# ByrneLite.net
KiCad netlist of a schematic drawn in EAGLE
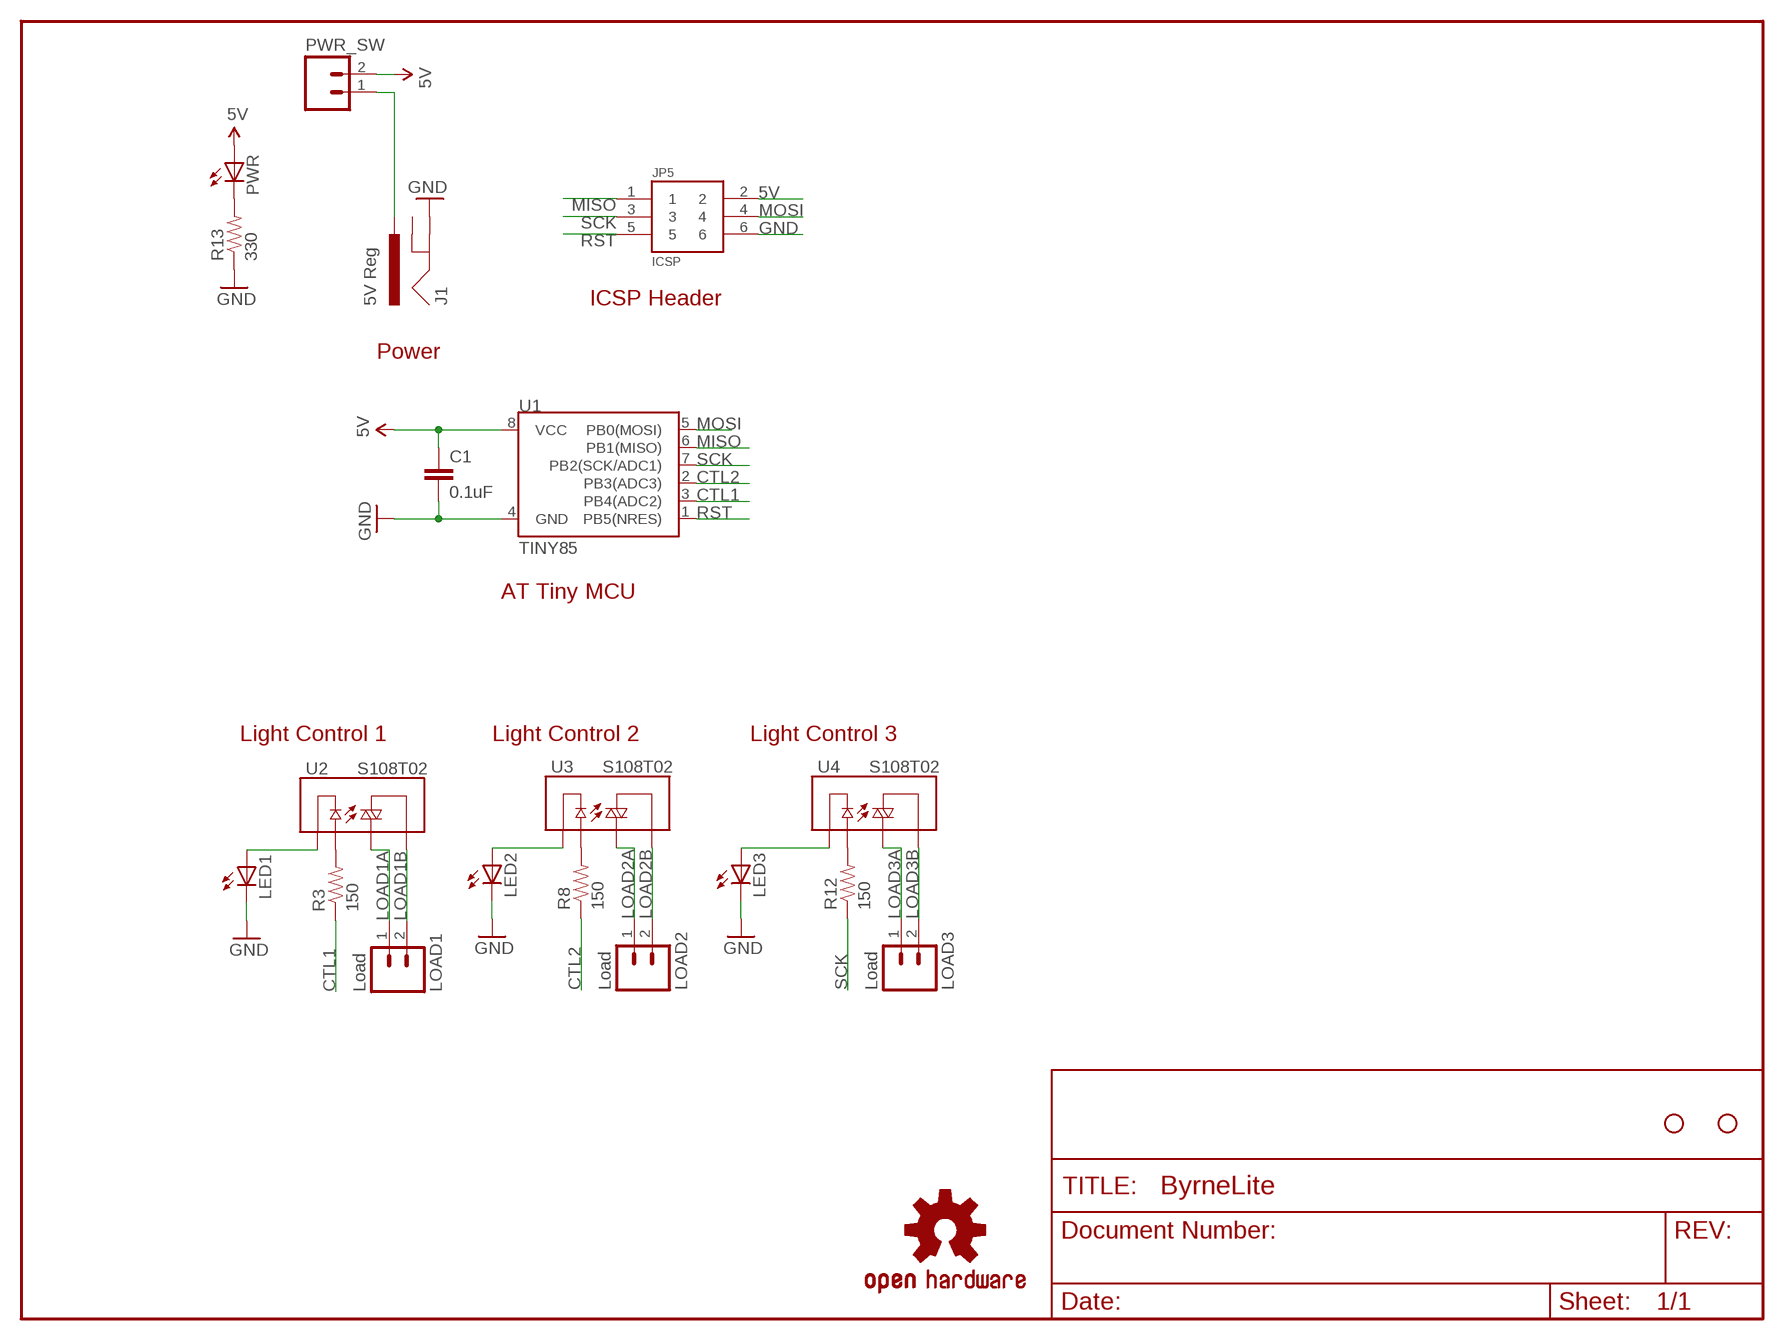
[diagram p0: schematic, sheet 1]

(export (version "E")
  (design (tool "Eeschema 10.0.6"))
  (components
    (comp (ref "C1")
      (value "0.1uF")
      (footprint "eagle-import:CAP-PTH-SMALL2")
      (libsource (lib "eagle-import") (part "CAPPTH2"))
    )
    (comp (ref "J1")
      (value "5V Reg")
      (footprint "eagle-import:POWER_JACK_PTH_LOCK")
      (libsource (lib "eagle-import") (part "POWER_JACKPTH_LOCK"))
    )
    (comp (ref "JP5")
      (value "ICSP")
      (footprint "eagle-import:2X3-SHROUDED")
      (libsource (lib "eagle-import") (part "M03X2"))
    )
    (comp (ref "LED1")
      (value "LED5MM")
      (footprint "eagle-import:LED5MM")
      (libsource (lib "eagle-import") (part "LED5MM"))
    )
    (comp (ref "LED2")
      (value "LED5MM")
      (footprint "eagle-import:LED5MM")
      (libsource (lib "eagle-import") (part "LED5MM"))
    )
    (comp (ref "LED3")
      (value "LED5MM")
      (footprint "eagle-import:LED5MM")
      (libsource (lib "eagle-import") (part "LED5MM"))
    )
    (comp (ref "LOAD1")
      (value "Load")
      (footprint "eagle-import:SCREWTERMINAL-5MM-2")
      (libsource (lib "eagle-import") (part "M025MM"))
    )
    (comp (ref "LOAD2")
      (value "Load")
      (footprint "eagle-import:SCREWTERMINAL-5MM-2")
      (libsource (lib "eagle-import") (part "M025MM"))
    )
    (comp (ref "LOAD3")
      (value "Load")
      (footprint "eagle-import:SCREWTERMINAL-5MM-2")
      (libsource (lib "eagle-import") (part "M025MM"))
    )
    (comp (ref "LOGO1")
      (value "OSHW-LOGOM")
      (footprint "eagle-import:OSHW-LOGO-M")
      (libsource (lib "eagle-import") (part "OSHW-LOGOM"))
    )
    (comp (ref "PWR")
      (value "LED3MM")
      (footprint "eagle-import:LED3MM")
      (libsource (lib "eagle-import") (part "LED3MM"))
    )
    (comp (ref "PWR_SW")
      (value "M02PTH3")
      (footprint "eagle-import:1X02_LONGPADS")
      (libsource (lib "eagle-import") (part "SparkFun-Connectors_M02PTH3"))
    )
    (comp (ref "R3")
      (value "150")
      (footprint "eagle-import:AXIAL-0.3")
      (libsource (lib "eagle-import") (part "RESISTORAXIAL-0.3"))
    )
    (comp (ref "R8")
      (value "150")
      (footprint "eagle-import:AXIAL-0.3")
      (libsource (lib "eagle-import") (part "RESISTORAXIAL-0.3"))
    )
    (comp (ref "R12")
      (value "150")
      (footprint "eagle-import:AXIAL-0.3")
      (libsource (lib "eagle-import") (part "RESISTORAXIAL-0.3"))
    )
    (comp (ref "R13")
      (value "330")
      (footprint "eagle-import:AXIAL-0.3")
      (libsource (lib "eagle-import") (part "RESISTORAXIAL-0.3"))
    )
    (comp (ref "STANDOFF2")
      (value "STAND-OFF")
      (footprint "eagle-import:STAND-OFF")
      (libsource (lib "eagle-import") (part "STAND-OFF"))
    )
    (comp (ref "STANDOFF4")
      (value "STAND-OFF")
      (footprint "eagle-import:STAND-OFF")
      (libsource (lib "eagle-import") (part "STAND-OFF"))
    )
    (comp (ref "U1")
      (value "TINY85")
      (footprint "eagle-import:DIP08")
      (fields (field (name "PROD_ID") "IC-09445"))
      (libsource (lib "eagle-import") (part "ATTINY45TINY85-20-DIP"))
    )
    (comp (ref "U2")
      (value "S108T02")
      (footprint "eagle-import:RELAY-S108T02")
      (libsource (lib "eagle-import") (part "RELAY-SOLIDSTATEPTH"))
    )
    (comp (ref "U3")
      (value "S108T02")
      (footprint "eagle-import:RELAY-S108T02")
      (libsource (lib "eagle-import") (part "RELAY-SOLIDSTATEPTH"))
    )
    (comp (ref "U4")
      (value "S108T02")
      (footprint "eagle-import:RELAY-S108T02")
      (libsource (lib "eagle-import") (part "RELAY-SOLIDSTATEPTH"))
    )
  )
  (nets
    (net (code "1") (name "/CTL1") (class "Default")
      (node (ref "R3") (pin "P$1") (pinfunction "1_P$1") (pintype "passive"))
      (node (ref "U1") (pin "3") (pinfunction "PB4(ADC2)_3") (pintype "bidirectional"))
    )
    (net (code "2") (name "/CTL2") (class "Default")
      (node (ref "R8") (pin "P$1") (pinfunction "1_P$1") (pintype "passive"))
      (node (ref "U1") (pin "2") (pinfunction "PB3(ADC3)_2") (pintype "bidirectional"))
    )
    (net (code "3") (name "/LOAD1A") (class "Default")
      (node (ref "LOAD1") (pin "1") (pinfunction "1_1") (pintype "passive"))
      (node (ref "U2") (pin "2") (pinfunction "T2_2") (pintype "bidirectional"))
    )
    (net (code "4") (name "/LOAD1B") (class "Default")
      (node (ref "LOAD1") (pin "2") (pinfunction "2_2") (pintype "passive"))
      (node (ref "U2") (pin "1") (pinfunction "T1_1") (pintype "bidirectional"))
    )
    (net (code "5") (name "/LOAD2A") (class "Default")
      (node (ref "LOAD2") (pin "1") (pinfunction "1_1") (pintype "passive"))
      (node (ref "U3") (pin "2") (pinfunction "T2_2") (pintype "bidirectional"))
    )
    (net (code "6") (name "/LOAD2B") (class "Default")
      (node (ref "LOAD2") (pin "2") (pinfunction "2_2") (pintype "passive"))
      (node (ref "U3") (pin "1") (pinfunction "T1_1") (pintype "bidirectional"))
    )
    (net (code "7") (name "/LOAD3A") (class "Default")
      (node (ref "LOAD3") (pin "1") (pinfunction "1_1") (pintype "passive"))
      (node (ref "U4") (pin "2") (pinfunction "T2_2") (pintype "bidirectional"))
    )
    (net (code "8") (name "/LOAD3B") (class "Default")
      (node (ref "LOAD3") (pin "2") (pinfunction "2_2") (pintype "passive"))
      (node (ref "U4") (pin "1") (pinfunction "T1_1") (pintype "bidirectional"))
    )
    (net (code "9") (name "/MISO") (class "Default")
      (node (ref "JP5") (pin "1") (pinfunction "1_1") (pintype "bidirectional"))
      (node (ref "U1") (pin "6") (pinfunction "PB1(MISO)_6") (pintype "bidirectional"))
    )
    (net (code "10") (name "/MOSI") (class "Default")
      (node (ref "JP5") (pin "4") (pinfunction "4_4") (pintype "bidirectional"))
      (node (ref "U1") (pin "5") (pinfunction "PB0(MOSI)_5") (pintype "bidirectional"))
    )
    (net (code "11") (name "/RST") (class "Default")
      (node (ref "JP5") (pin "5") (pinfunction "5_5") (pintype "bidirectional"))
      (node (ref "U1") (pin "1") (pinfunction "PB5(NRES)_1") (pintype "bidirectional"))
    )
    (net (code "12") (name "/SCK") (class "Default")
      (node (ref "JP5") (pin "3") (pinfunction "3_3") (pintype "bidirectional"))
      (node (ref "R12") (pin "P$1") (pinfunction "1_P$1") (pintype "passive"))
      (node (ref "U1") (pin "7") (pinfunction "PB2(SCK/ADC1)_7") (pintype "bidirectional"))
    )
    (net (code "13") (name "5V") (class "Default")
      (node (ref "C1") (pin "1") (pinfunction "1_1") (pintype "passive"))
      (node (ref "JP5") (pin "2") (pinfunction "2_2") (pintype "bidirectional"))
      (node (ref "PWR") (pin "A") (pinfunction "A_A") (pintype "passive"))
      (node (ref "PWR_SW") (pin "2") (pinfunction "2_2") (pintype "passive"))
      (node (ref "U1") (pin "8") (pinfunction "VCC_8") (pintype "bidirectional"))
    )
    (net (code "14") (name "GND") (class "Default")
      (node (ref "C1") (pin "2") (pinfunction "2_2") (pintype "passive"))
      (node (ref "J1") (pin "GND") (pinfunction "GND_GND") (pintype "bidirectional"))
      (node (ref "JP5") (pin "6") (pinfunction "6_6") (pintype "bidirectional"))
      (node (ref "LED1") (pin "K") (pinfunction "C_K") (pintype "passive"))
      (node (ref "LED2") (pin "K") (pinfunction "C_K") (pintype "passive"))
      (node (ref "LED3") (pin "K") (pinfunction "C_K") (pintype "passive"))
      (node (ref "R13") (pin "P$1") (pinfunction "1_P$1") (pintype "passive"))
      (node (ref "U1") (pin "4") (pinfunction "GND_4") (pintype "bidirectional"))
    )
    (net (code "15") (name "Net-(J1-PadPWR)") (class "Default")
      (node (ref "J1") (pin "PWR") (pinfunction "PWR_PWR") (pintype "bidirectional"))
      (node (ref "PWR_SW") (pin "1") (pinfunction "1_1") (pintype "passive"))
    )
    (net (code "16") (name "Net-(PWR-C)") (class "Default")
      (node (ref "PWR") (pin "K") (pinfunction "C_K") (pintype "passive"))
      (node (ref "R13") (pin "P$2") (pinfunction "2_P$2") (pintype "passive"))
    )
    (net (code "17") (name "Net-(R3-2)") (class "Default")
      (node (ref "R3") (pin "P$2") (pinfunction "2_P$2") (pintype "passive"))
      (node (ref "U2") (pin "3") (pinfunction "+_3") (pintype "bidirectional"))
    )
    (net (code "18") (name "Net-(R8-2)") (class "Default")
      (node (ref "R8") (pin "P$2") (pinfunction "2_P$2") (pintype "passive"))
      (node (ref "U3") (pin "3") (pinfunction "+_3") (pintype "bidirectional"))
    )
    (net (code "19") (name "Net-(R12-2)") (class "Default")
      (node (ref "R12") (pin "P$2") (pinfunction "2_P$2") (pintype "passive"))
      (node (ref "U4") (pin "3") (pinfunction "+_3") (pintype "bidirectional"))
    )
    (net (code "20") (name "Net-(U2--)") (class "Default")
      (node (ref "LED1") (pin "A") (pinfunction "A_A") (pintype "passive"))
      (node (ref "U2") (pin "4") (pinfunction "-_4") (pintype "bidirectional"))
    )
    (net (code "21") (name "Net-(U3--)") (class "Default")
      (node (ref "LED2") (pin "A") (pinfunction "A_A") (pintype "passive"))
      (node (ref "U3") (pin "4") (pinfunction "-_4") (pintype "bidirectional"))
    )
    (net (code "22") (name "Net-(U4--)") (class "Default")
      (node (ref "LED3") (pin "A") (pinfunction "A_A") (pintype "passive"))
      (node (ref "U4") (pin "4") (pinfunction "-_4") (pintype "bidirectional"))
    )
    (net (code "23") (name "unconnected-(J1-PadGNDBREAK)") (class "Default")
      (node (ref "J1") (pin "GNDBREAK") (pinfunction "GNDBREAK_GNDBREAK") (pintype "bidirectional"))
    )
  )
)
